# Booster_Sensors.net
KiCad netlist of a schematic drawn in Altium Designer
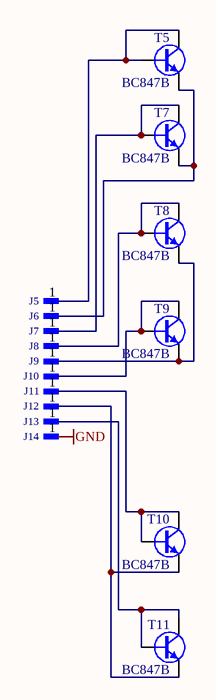
[diagram p0: Booster_Sensors.SchDoc]

(export (version "E")
  (design (tool "Eeschema 10.0.6"))
  (components
    (comp (ref "J5")
      (value "SMD Pad")
      (footprint "R700X200")
      (description "Single SMD Pad")
      (fields (field (name "PART NUMBER") "SMD_PAD_7X2MM") (field (name "AUTHOR") "CERN DEM MR"))
      (libsource (lib "Eletro-mechanical") (part "Single SMD Pad"))
    )
    (comp (ref "J6")
      (value "SMD Pad")
      (footprint "R700X200")
      (description "Single SMD Pad")
      (fields (field (name "PART NUMBER") "SMD_PAD_7X2MM") (field (name "AUTHOR") "CERN DEM MR"))
      (libsource (lib "Eletro-mechanical") (part "Single SMD Pad"))
    )
    (comp (ref "J7")
      (value "SMD Pad")
      (footprint "R700X200")
      (description "Single SMD Pad")
      (fields (field (name "PART NUMBER") "SMD_PAD_7X2MM") (field (name "AUTHOR") "CERN DEM MR"))
      (libsource (lib "Eletro-mechanical") (part "Single SMD Pad"))
    )
    (comp (ref "J8")
      (value "SMD Pad")
      (footprint "R700X200")
      (description "Single SMD Pad")
      (fields (field (name "PART NUMBER") "SMD_PAD_7X2MM") (field (name "AUTHOR") "CERN DEM MR"))
      (libsource (lib "Eletro-mechanical") (part "Single SMD Pad"))
    )
    (comp (ref "J9")
      (value "SMD Pad")
      (footprint "R700X200")
      (description "Single SMD Pad")
      (fields (field (name "PART NUMBER") "SMD_PAD_7X2MM") (field (name "AUTHOR") "CERN DEM MR"))
      (libsource (lib "Eletro-mechanical") (part "Single SMD Pad"))
    )
    (comp (ref "J10")
      (value "SMD Pad")
      (footprint "R700X200")
      (description "Single SMD Pad")
      (fields (field (name "PART NUMBER") "SMD_PAD_7X2MM") (field (name "AUTHOR") "CERN DEM MR"))
      (libsource (lib "Eletro-mechanical") (part "Single SMD Pad"))
    )
    (comp (ref "J11")
      (value "SMD Pad")
      (footprint "R700X200")
      (description "Single SMD Pad")
      (fields (field (name "PART NUMBER") "SMD_PAD_7X2MM") (field (name "AUTHOR") "CERN DEM MR"))
      (libsource (lib "Eletro-mechanical") (part "Single SMD Pad"))
    )
    (comp (ref "J12")
      (value "SMD Pad")
      (footprint "R700X200")
      (description "Single SMD Pad")
      (fields (field (name "PART NUMBER") "SMD_PAD_7X2MM") (field (name "AUTHOR") "CERN DEM MR"))
      (libsource (lib "Eletro-mechanical") (part "Single SMD Pad"))
    )
    (comp (ref "J13")
      (value "SMD Pad")
      (footprint "R700X200")
      (description "Single SMD Pad")
      (fields (field (name "PART NUMBER") "SMD_PAD_7X2MM") (field (name "AUTHOR") "CERN DEM MR"))
      (libsource (lib "Eletro-mechanical") (part "Single SMD Pad"))
    )
    (comp (ref "J14")
      (value "SMD Pad")
      (footprint "R700X200")
      (description "Single SMD Pad")
      (fields (field (name "PART NUMBER") "SMD_PAD_7X2MM") (field (name "AUTHOR") "CERN DEM MR"))
      (libsource (lib "Eletro-mechanical") (part "Single SMD Pad"))
    )
    (comp (ref "T5")
      (value "BC847B")
      (footprint "SOT95P230X110-3N")
      (description "NPN Transistor")
      (fields (field (name "MANUFACTURER") "NXP SEMICONDUCTORS") (field (name "AUTHOR") "CERN DEM JLC"))
      (libsource (lib "ICs And Semiconductors") (part "NPN B1 E2 C3"))
    )
    (comp (ref "T7")
      (value "BC847B")
      (footprint "SOT95P230X110-3N")
      (description "NPN Transistor")
      (fields (field (name "MANUFACTURER") "NXP SEMICONDUCTORS") (field (name "AUTHOR") "CERN DEM JLC"))
      (libsource (lib "ICs And Semiconductors") (part "NPN B1 E2 C3"))
    )
    (comp (ref "T8")
      (value "BC847B")
      (footprint "SOT95P230X110-3N")
      (description "NPN Transistor")
      (fields (field (name "MANUFACTURER") "NXP SEMICONDUCTORS") (field (name "AUTHOR") "CERN DEM JLC"))
      (libsource (lib "ICs And Semiconductors") (part "NPN B1 E2 C3"))
    )
    (comp (ref "T9")
      (value "BC847B")
      (footprint "SOT95P230X110-3N")
      (description "NPN Transistor")
      (fields (field (name "MANUFACTURER") "NXP SEMICONDUCTORS") (field (name "AUTHOR") "CERN DEM JLC"))
      (libsource (lib "ICs And Semiconductors") (part "NPN B1 E2 C3"))
    )
    (comp (ref "T10")
      (value "BC847B")
      (footprint "SOT95P230X110-3N")
      (description "NPN Transistor")
      (fields (field (name "MANUFACTURER") "NXP SEMICONDUCTORS") (field (name "AUTHOR") "CERN DEM JLC"))
      (libsource (lib "ICs And Semiconductors") (part "NPN B1 E2 C3"))
    )
    (comp (ref "T11")
      (value "BC847B")
      (footprint "SOT95P230X110-3N")
      (description "NPN Transistor")
      (fields (field (name "MANUFACTURER") "NXP SEMICONDUCTORS") (field (name "AUTHOR") "CERN DEM JLC"))
      (libsource (lib "ICs And Semiconductors") (part "NPN B1 E2 C3"))
    )
  )
  (nets
    (net (code "1") (name "GND") (class "Default")
      (node (ref "J14") (pin "1") (pinfunction "1_1") (pintype "bidirectional"))
    )
    (net (code "2") (name "Net-(T5-B)") (class "Default")
      (node (ref "J5") (pin "1") (pinfunction "1_1") (pintype "bidirectional"))
      (node (ref "T5") (pin "1") (pinfunction "B_1") (pintype "passive"))
      (node (ref "T5") (pin "3") (pinfunction "C_3") (pintype "passive"))
    )
    (net (code "3") (name "Net-(T5-E)") (class "Default")
      (node (ref "J6") (pin "1") (pinfunction "1_1") (pintype "bidirectional"))
      (node (ref "T5") (pin "2") (pinfunction "E_2") (pintype "passive"))
      (node (ref "T7") (pin "2") (pinfunction "E_2") (pintype "passive"))
    )
    (net (code "4") (name "Net-(T7-B)") (class "Default")
      (node (ref "J7") (pin "1") (pinfunction "1_1") (pintype "bidirectional"))
      (node (ref "T7") (pin "1") (pinfunction "B_1") (pintype "passive"))
      (node (ref "T7") (pin "3") (pinfunction "C_3") (pintype "passive"))
    )
    (net (code "5") (name "Net-(T8-B)") (class "Default")
      (node (ref "J8") (pin "1") (pinfunction "1_1") (pintype "bidirectional"))
      (node (ref "T8") (pin "1") (pinfunction "B_1") (pintype "passive"))
      (node (ref "T8") (pin "3") (pinfunction "C_3") (pintype "passive"))
    )
    (net (code "6") (name "Net-(T8-E)") (class "Default")
      (node (ref "J9") (pin "1") (pinfunction "1_1") (pintype "bidirectional"))
      (node (ref "T8") (pin "2") (pinfunction "E_2") (pintype "passive"))
      (node (ref "T9") (pin "2") (pinfunction "E_2") (pintype "passive"))
    )
    (net (code "7") (name "Net-(T9-B)") (class "Default")
      (node (ref "J10") (pin "1") (pinfunction "1_1") (pintype "bidirectional"))
      (node (ref "T9") (pin "1") (pinfunction "B_1") (pintype "passive"))
      (node (ref "T9") (pin "3") (pinfunction "C_3") (pintype "passive"))
    )
    (net (code "8") (name "Net-(T10-B)") (class "Default")
      (node (ref "J11") (pin "1") (pinfunction "1_1") (pintype "bidirectional"))
      (node (ref "T10") (pin "1") (pinfunction "B_1") (pintype "passive"))
      (node (ref "T10") (pin "3") (pinfunction "C_3") (pintype "passive"))
    )
    (net (code "9") (name "Net-(T10-E)") (class "Default")
      (node (ref "J12") (pin "1") (pinfunction "1_1") (pintype "bidirectional"))
      (node (ref "T10") (pin "2") (pinfunction "E_2") (pintype "passive"))
      (node (ref "T11") (pin "2") (pinfunction "E_2") (pintype "passive"))
    )
    (net (code "10") (name "Net-(T11-B)") (class "Default")
      (node (ref "J13") (pin "1") (pinfunction "1_1") (pintype "bidirectional"))
      (node (ref "T11") (pin "1") (pinfunction "B_1") (pintype "passive"))
      (node (ref "T11") (pin "3") (pinfunction "C_3") (pintype "passive"))
    )
  )
)
